# Aquarium-controller.net
KiCad netlist of a schematic drawn in EAGLE
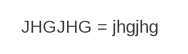
[diagram p0: schematic, sheet 1, part 1 of 2]
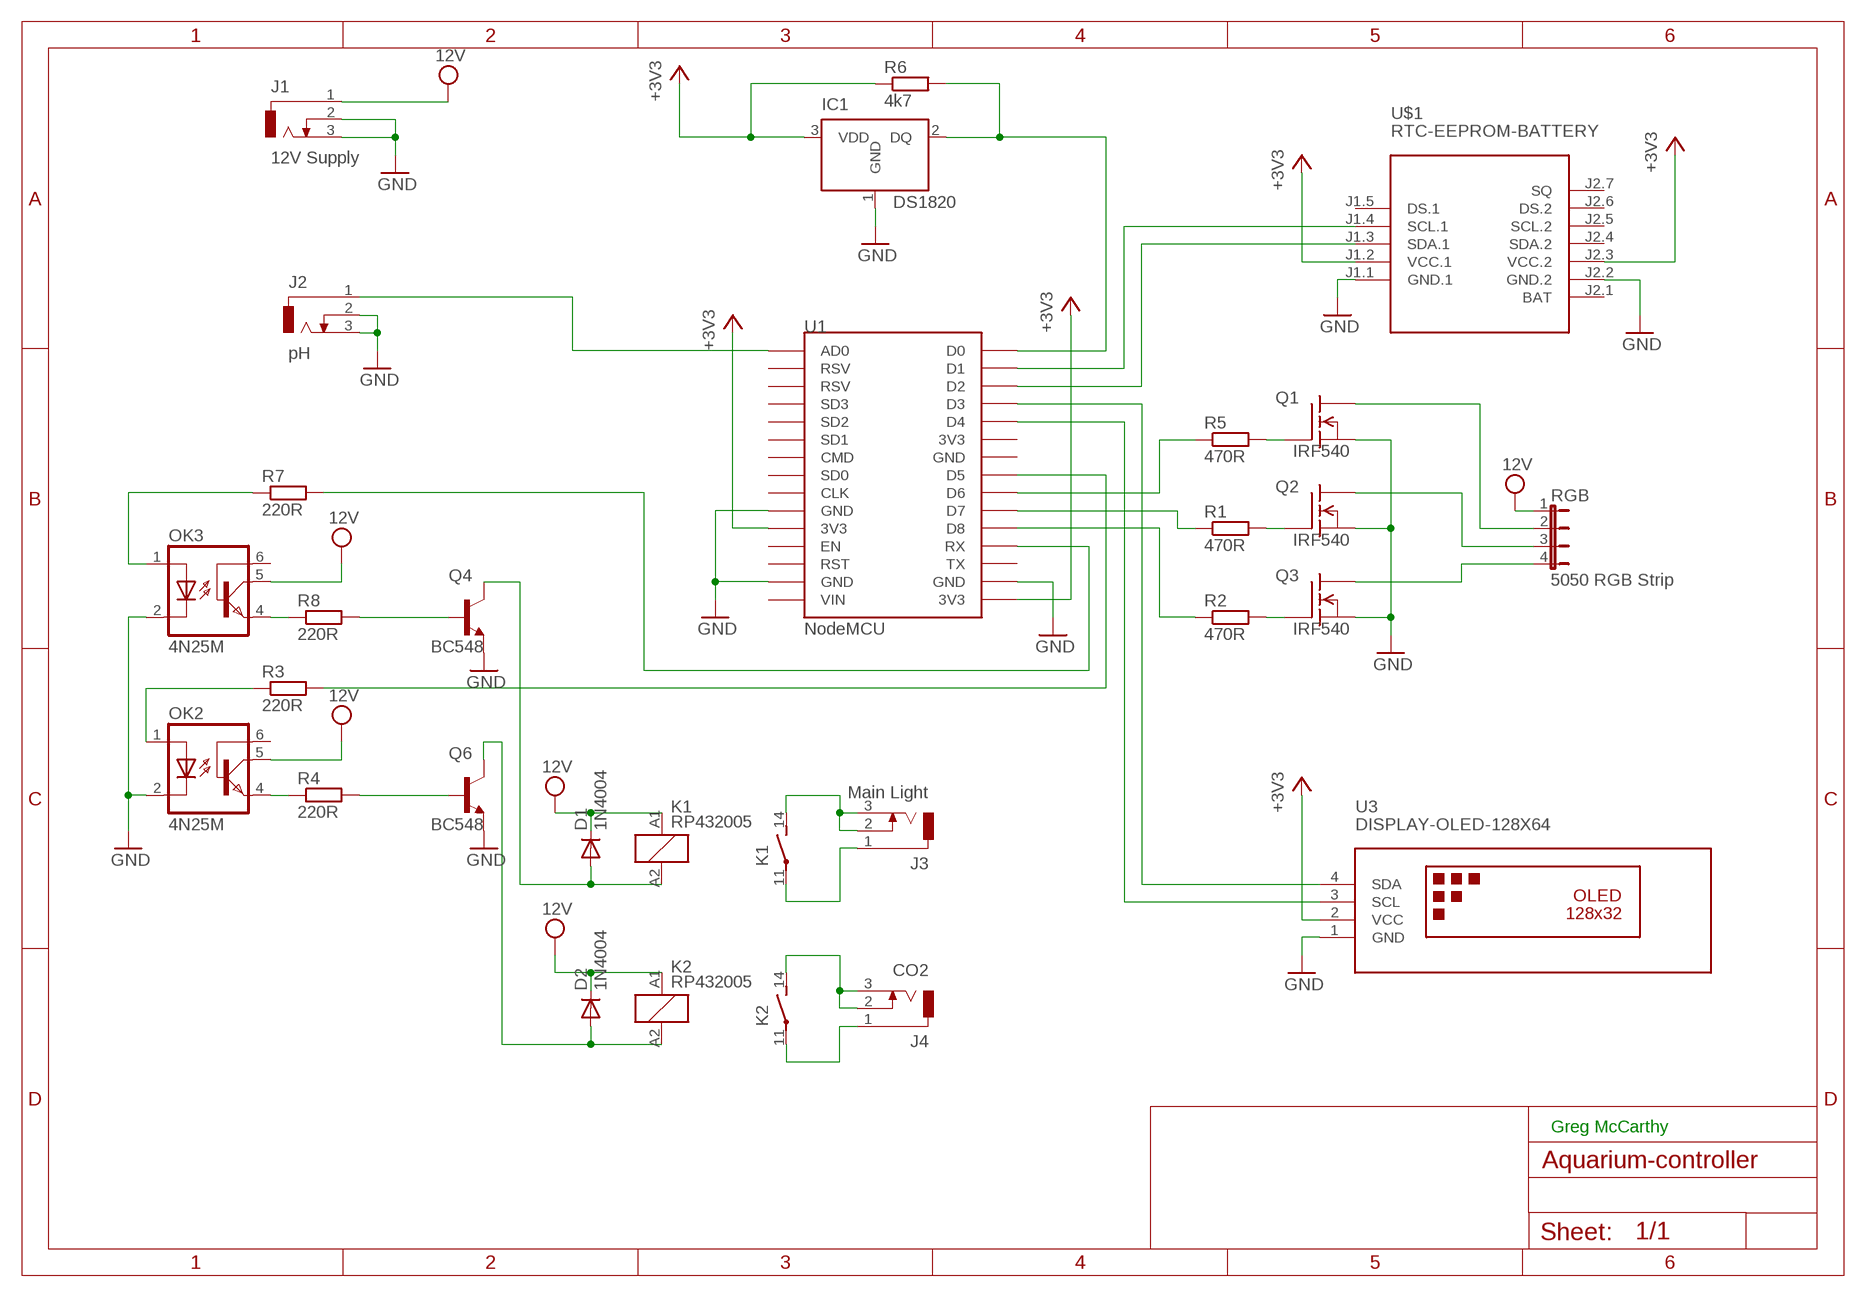
[diagram p1: schematic, sheet 1, part 2 of 2]

(export (version "E")
  (design (tool "Eeschema 10.0.6"))
  (components
    (comp (ref "D1")
      (value "1N4004")
      (footprint "eagle-import:DO41-10")
      (libsource (lib "eagle-import") (part "1N4004"))
    )
    (comp (ref "D2")
      (value "1N4004")
      (footprint "eagle-import:DO41-10")
      (libsource (lib "eagle-import") (part "1N4004"))
    )
    (comp (ref "IC1")
      (value "DS1820")
      (footprint "eagle-import:TO-92")
      (libsource (lib "eagle-import") (part "DS1820"))
    )
    (comp (ref "J1")
      (value "12V Supply")
      (footprint "eagle-import:DCJ0202")
      (libsource (lib "eagle-import") (part "DCJ0202"))
    )
    (comp (ref "J2")
      (value "pH")
      (footprint "eagle-import:DCJ0202")
      (libsource (lib "eagle-import") (part "DCJ0202"))
    )
    (comp (ref "J3")
      (value "Main Light")
      (footprint "eagle-import:DCJ0202")
      (libsource (lib "eagle-import") (part "DCJ0202"))
    )
    (comp (ref "J4")
      (value "CO2")
      (footprint "eagle-import:DCJ0202")
      (libsource (lib "eagle-import") (part "DCJ0202"))
    )
    (comp (ref "K1")
      (value "RP432005")
      (footprint "eagle-import:RT-N_O12A3.5")
      (libsource (lib "eagle-import") (part "RP?324005"))
    )
    (comp (ref "K2")
      (value "RP432005")
      (footprint "eagle-import:RT-N_O12A3.5")
      (libsource (lib "eagle-import") (part "RP?324005"))
    )
    (comp (ref "OK2")
      (value "4N25M")
      (footprint "eagle-import:DIL06")
      (fields (field (name "MPN") "4N25-M"))
      (libsource (lib "eagle-import") (part "4N?M25"))
    )
    (comp (ref "OK3")
      (value "4N25M")
      (footprint "eagle-import:DIL06")
      (fields (field (name "MPN") "4N25-M"))
      (libsource (lib "eagle-import") (part "4N?M25"))
    )
    (comp (ref "Q1")
      (value "IRF540")
      (footprint "eagle-import:TO220")
      (libsource (lib "eagle-import") (part "IRF540"))
    )
    (comp (ref "Q2")
      (value "IRF540")
      (footprint "eagle-import:TO220")
      (libsource (lib "eagle-import") (part "IRF540"))
    )
    (comp (ref "Q3")
      (value "IRF540")
      (footprint "eagle-import:TO220")
      (libsource (lib "eagle-import") (part "IRF540"))
    )
    (comp (ref "Q4")
      (value "BC548")
      (footprint "eagle-import:TO92-EBC")
      (libsource (lib "eagle-import") (part "BC548"))
    )
    (comp (ref "Q6")
      (value "BC548")
      (footprint "eagle-import:TO92-EBC")
      (libsource (lib "eagle-import") (part "BC548"))
    )
    (comp (ref "R1")
      (value "470R")
      (footprint "eagle-import:0204_7")
      (libsource (lib "eagle-import") (part "R0204/7"))
    )
    (comp (ref "R2")
      (value "470R")
      (footprint "eagle-import:0204_7")
      (libsource (lib "eagle-import") (part "R0204/7"))
    )
    (comp (ref "R3")
      (value "220R")
      (footprint "eagle-import:0204_7")
      (libsource (lib "eagle-import") (part "R0204/7"))
    )
    (comp (ref "R4")
      (value "220R")
      (footprint "eagle-import:0204_7")
      (libsource (lib "eagle-import") (part "R0204/7"))
    )
    (comp (ref "R5")
      (value "470R")
      (footprint "eagle-import:0204_7")
      (libsource (lib "eagle-import") (part "R0204/7"))
    )
    (comp (ref "R6")
      (value "4k7")
      (footprint "eagle-import:0204_7")
      (libsource (lib "eagle-import") (part "R0204/7"))
    )
    (comp (ref "R7")
      (value "220R")
      (footprint "eagle-import:0204_7")
      (libsource (lib "eagle-import") (part "R0204/7"))
    )
    (comp (ref "R8")
      (value "220R")
      (footprint "eagle-import:0204_7")
      (libsource (lib "eagle-import") (part "R0204/7"))
    )
    (comp (ref "RGB")
      (value "5050 RGB Strip")
      (footprint "eagle-import:JP4")
      (libsource (lib "eagle-import") (part "JP4E"))
    )
    (comp (ref "U$1")
      (value "RTC-EEPROM-BATTERY")
      (footprint "eagle-import:RTC-EEPROM-BATTERY")
      (libsource (lib "eagle-import") (part "RTC-EEPROM-BATTERY"))
    )
    (comp (ref "U1")
      (value "NodeMCU")
      (footprint "eagle-import:ESP12E_DEVKIT")
      (libsource (lib "eagle-import") (part "ESP12E_DEVKIT"))
    )
    (comp (ref "U3")
      (value "DISPLAY-OLED-128X64")
      (footprint "eagle-import:DISPLAY-OLED-128X32")
      (libsource (lib "eagle-import") (part "DISPLAY-OLED-128X32"))
    )
  )
  (nets
    (net (code "1") (name "+3V3") (class "Default")
      (node (ref "IC1") (pin "3") (pinfunction "VDD_3") (pintype "input"))
      (node (ref "R6") (pin "1") (pinfunction "1_1") (pintype "passive"))
      (node (ref "U$1") (pin "J1.2") (pinfunction "VCC.1_J1.2") (pintype "power_in"))
      (node (ref "U$1") (pin "J2.3") (pinfunction "VCC.2_J2.3") (pintype "power_in"))
      (node (ref "U1") (pin "3V3@0") (pinfunction "3V3_3V3@0") (pintype "bidirectional"))
      (node (ref "U1") (pin "3V3@2") (pinfunction "3V3_3V3@2") (pintype "bidirectional"))
      (node (ref "U3") (pin "2") (pinfunction "VCC_2") (pintype "power_in"))
    )
    (net (code "2") (name "12V") (class "Default")
      (node (ref "D1") (pin "C") (pinfunction "C_C") (pintype "passive"))
      (node (ref "D2") (pin "C") (pinfunction "C_C") (pintype "passive"))
      (node (ref "J1") (pin "1") (pinfunction "1_1") (pintype "passive"))
      (node (ref "K1") (pin "A1") (pinfunction "1_A1") (pintype "passive"))
      (node (ref "K2") (pin "A1") (pinfunction "1_A1") (pintype "passive"))
      (node (ref "OK2") (pin "5") (pinfunction "COL_5") (pintype "passive"))
      (node (ref "OK3") (pin "5") (pinfunction "COL_5") (pintype "passive"))
      (node (ref "RGB") (pin "1") (pinfunction "1_1") (pintype "passive"))
    )
    (net (code "3") (name "GND") (class "Default")
      (node (ref "IC1") (pin "1") (pinfunction "GND_1") (pintype "power_in"))
      (node (ref "J1") (pin "2") (pinfunction "2_2") (pintype "passive"))
      (node (ref "J1") (pin "3") (pinfunction "3_3") (pintype "passive"))
      (node (ref "J2") (pin "2") (pinfunction "2_2") (pintype "passive"))
      (node (ref "J2") (pin "3") (pinfunction "3_3") (pintype "passive"))
      (node (ref "OK2") (pin "2") (pinfunction "C_2") (pintype "passive"))
      (node (ref "OK3") (pin "2") (pinfunction "C_2") (pintype "passive"))
      (node (ref "Q1") (pin "3") (pinfunction "S_3") (pintype "passive"))
      (node (ref "Q2") (pin "3") (pinfunction "S_3") (pintype "passive"))
      (node (ref "Q3") (pin "3") (pinfunction "S_3") (pintype "passive"))
      (node (ref "Q4") (pin "E") (pinfunction "E_E") (pintype "passive"))
      (node (ref "Q6") (pin "E") (pinfunction "E_E") (pintype "passive"))
      (node (ref "U$1") (pin "J1.1") (pinfunction "GND.1_J1.1") (pintype "power_in"))
      (node (ref "U$1") (pin "J2.2") (pinfunction "GND.2_J2.2") (pintype "power_in"))
      (node (ref "U1") (pin "GND@0") (pinfunction "GND_GND@0") (pintype "bidirectional"))
      (node (ref "U1") (pin "GND@1") (pinfunction "GND_GND@1") (pintype "bidirectional"))
      (node (ref "U1") (pin "GND@3") (pinfunction "GND_GND@3") (pintype "bidirectional"))
      (node (ref "U3") (pin "1") (pinfunction "GND_1") (pintype "power_in"))
    )
    (net (code "4") (name "Net-(IC1-DQ)") (class "Default")
      (node (ref "IC1") (pin "2") (pinfunction "DQ_2") (pintype "output"))
      (node (ref "R6") (pin "2") (pinfunction "2_2") (pintype "passive"))
      (node (ref "U1") (pin "D0") (pinfunction "D0_D0") (pintype "bidirectional"))
    )
    (net (code "5") (name "Net-(J2-Pad1)") (class "Default")
      (node (ref "J2") (pin "1") (pinfunction "1_1") (pintype "passive"))
      (node (ref "U1") (pin "AD0") (pinfunction "AD0_AD0") (pintype "bidirectional"))
    )
    (net (code "6") (name "Net-(K1A-2)") (class "Default")
      (node (ref "D1") (pin "A") (pinfunction "A_A") (pintype "passive"))
      (node (ref "K1") (pin "A2") (pinfunction "2_A2") (pintype "passive"))
      (node (ref "Q4") (pin "C") (pinfunction "C_C") (pintype "passive"))
    )
    (net (code "7") (name "Net-(K1B-P)") (class "Default")
      (node (ref "J3") (pin "1") (pinfunction "1_1") (pintype "passive"))
      (node (ref "K1") (pin "11") (pinfunction "P_11") (pintype "passive"))
    )
    (net (code "8") (name "Net-(K1B-S)") (class "Default")
      (node (ref "J3") (pin "2") (pinfunction "2_2") (pintype "passive"))
      (node (ref "J3") (pin "3") (pinfunction "3_3") (pintype "passive"))
      (node (ref "K1") (pin "14") (pinfunction "S_14") (pintype "passive"))
    )
    (net (code "9") (name "Net-(K2A-2)") (class "Default")
      (node (ref "D2") (pin "A") (pinfunction "A_A") (pintype "passive"))
      (node (ref "K2") (pin "A2") (pinfunction "2_A2") (pintype "passive"))
      (node (ref "Q6") (pin "C") (pinfunction "C_C") (pintype "passive"))
    )
    (net (code "10") (name "Net-(K2B-P)") (class "Default")
      (node (ref "J4") (pin "1") (pinfunction "1_1") (pintype "passive"))
      (node (ref "K2") (pin "11") (pinfunction "P_11") (pintype "passive"))
    )
    (net (code "11") (name "Net-(K2B-S)") (class "Default")
      (node (ref "J4") (pin "2") (pinfunction "2_2") (pintype "passive"))
      (node (ref "J4") (pin "3") (pinfunction "3_3") (pintype "passive"))
      (node (ref "K2") (pin "14") (pinfunction "S_14") (pintype "passive"))
    )
    (net (code "12") (name "Net-(OK2-A)") (class "Default")
      (node (ref "OK2") (pin "1") (pinfunction "A_1") (pintype "passive"))
      (node (ref "R3") (pin "1") (pinfunction "1_1") (pintype "passive"))
    )
    (net (code "13") (name "Net-(OK2-EMI)") (class "Default")
      (node (ref "OK2") (pin "4") (pinfunction "EMI_4") (pintype "passive"))
      (node (ref "R4") (pin "1") (pinfunction "1_1") (pintype "passive"))
    )
    (net (code "14") (name "Net-(OK3-A)") (class "Default")
      (node (ref "OK3") (pin "1") (pinfunction "A_1") (pintype "passive"))
      (node (ref "R7") (pin "1") (pinfunction "1_1") (pintype "passive"))
    )
    (net (code "15") (name "Net-(OK3-EMI)") (class "Default")
      (node (ref "OK3") (pin "4") (pinfunction "EMI_4") (pintype "passive"))
      (node (ref "R8") (pin "1") (pinfunction "1_1") (pintype "passive"))
    )
    (net (code "16") (name "Net-(Q1-D)") (class "Default")
      (node (ref "Q1") (pin "2") (pinfunction "D_2") (pintype "passive"))
      (node (ref "RGB") (pin "2") (pinfunction "2_2") (pintype "passive"))
    )
    (net (code "17") (name "Net-(Q1-G)") (class "Default")
      (node (ref "Q1") (pin "1") (pinfunction "G_1") (pintype "passive"))
      (node (ref "R5") (pin "2") (pinfunction "2_2") (pintype "passive"))
    )
    (net (code "18") (name "Net-(Q2-D)") (class "Default")
      (node (ref "Q2") (pin "2") (pinfunction "D_2") (pintype "passive"))
      (node (ref "RGB") (pin "3") (pinfunction "3_3") (pintype "passive"))
    )
    (net (code "19") (name "Net-(Q2-G)") (class "Default")
      (node (ref "Q2") (pin "1") (pinfunction "G_1") (pintype "passive"))
      (node (ref "R1") (pin "2") (pinfunction "2_2") (pintype "passive"))
    )
    (net (code "20") (name "Net-(Q3-D)") (class "Default")
      (node (ref "Q3") (pin "2") (pinfunction "D_2") (pintype "passive"))
      (node (ref "RGB") (pin "4") (pinfunction "4_4") (pintype "passive"))
    )
    (net (code "21") (name "Net-(Q3-G)") (class "Default")
      (node (ref "Q3") (pin "1") (pinfunction "G_1") (pintype "passive"))
      (node (ref "R2") (pin "2") (pinfunction "2_2") (pintype "passive"))
    )
    (net (code "22") (name "Net-(Q4-PadB)") (class "Default")
      (node (ref "Q4") (pin "B") (pinfunction "B_B") (pintype "passive"))
      (node (ref "R8") (pin "2") (pinfunction "2_2") (pintype "passive"))
    )
    (net (code "23") (name "Net-(Q6-PadB)") (class "Default")
      (node (ref "Q6") (pin "B") (pinfunction "B_B") (pintype "passive"))
      (node (ref "R4") (pin "2") (pinfunction "2_2") (pintype "passive"))
    )
    (net (code "24") (name "Net-(R1-Pad1)") (class "Default")
      (node (ref "R1") (pin "1") (pinfunction "1_1") (pintype "passive"))
      (node (ref "U1") (pin "D7") (pinfunction "D7_D7") (pintype "bidirectional"))
    )
    (net (code "25") (name "Net-(R2-Pad1)") (class "Default")
      (node (ref "R2") (pin "1") (pinfunction "1_1") (pintype "passive"))
      (node (ref "U1") (pin "D8") (pinfunction "D8_D8") (pintype "bidirectional"))
    )
    (net (code "26") (name "Net-(R3-Pad2)") (class "Default")
      (node (ref "R3") (pin "2") (pinfunction "2_2") (pintype "passive"))
      (node (ref "U1") (pin "D5") (pinfunction "D5_D5") (pintype "bidirectional"))
    )
    (net (code "27") (name "Net-(R5-Pad1)") (class "Default")
      (node (ref "R5") (pin "1") (pinfunction "1_1") (pintype "passive"))
      (node (ref "U1") (pin "D6") (pinfunction "D6_D6") (pintype "bidirectional"))
    )
    (net (code "28") (name "Net-(R7-Pad2)") (class "Default")
      (node (ref "R7") (pin "2") (pinfunction "2_2") (pintype "passive"))
      (node (ref "U1") (pin "RX") (pinfunction "RX_RX") (pintype "bidirectional"))
    )
    (net (code "29") (name "Net-(U$1-SCL.1)") (class "Default")
      (node (ref "U$1") (pin "J1.4") (pinfunction "SCL.1_J1.4") (pintype "bidirectional"))
      (node (ref "U1") (pin "D1") (pinfunction "D1_D1") (pintype "bidirectional"))
    )
    (net (code "30") (name "Net-(U$1-SDA.1)") (class "Default")
      (node (ref "U$1") (pin "J1.3") (pinfunction "SDA.1_J1.3") (pintype "bidirectional"))
      (node (ref "U1") (pin "D2") (pinfunction "D2_D2") (pintype "bidirectional"))
    )
    (net (code "31") (name "Net-(U3-SCL)") (class "Default")
      (node (ref "U1") (pin "D4") (pinfunction "D4_D4") (pintype "bidirectional"))
      (node (ref "U3") (pin "3") (pinfunction "SCL_3") (pintype "bidirectional"))
    )
    (net (code "32") (name "Net-(U3-SDA)") (class "Default")
      (node (ref "U1") (pin "D3") (pinfunction "D3_D3") (pintype "bidirectional"))
      (node (ref "U3") (pin "4") (pinfunction "SDA_4") (pintype "bidirectional"))
    )
    (net (code "33") (name "unconnected-(OK2-BAS-Pad6)") (class "Default")
      (node (ref "OK2") (pin "6") (pinfunction "BAS_6") (pintype "passive"))
    )
    (net (code "34") (name "unconnected-(OK3-BAS-Pad6)") (class "Default")
      (node (ref "OK3") (pin "6") (pinfunction "BAS_6") (pintype "passive"))
    )
    (net (code "35") (name "unconnected-(U$1-BAT-PadJ2.1)") (class "Default")
      (node (ref "U$1") (pin "J2.1") (pinfunction "BAT_J2.1") (pintype "bidirectional"))
    )
    (net (code "36") (name "unconnected-(U$1-DS.1-PadJ1.5)") (class "Default")
      (node (ref "U$1") (pin "J1.5") (pinfunction "DS.1_J1.5") (pintype "bidirectional"))
    )
    (net (code "37") (name "unconnected-(U$1-DS.2-PadJ2.6)") (class "Default")
      (node (ref "U$1") (pin "J2.6") (pinfunction "DS.2_J2.6") (pintype "bidirectional"))
    )
    (net (code "38") (name "unconnected-(U$1-SCL.2-PadJ2.5)") (class "Default")
      (node (ref "U$1") (pin "J2.5") (pinfunction "SCL.2_J2.5") (pintype "bidirectional"))
    )
    (net (code "39") (name "unconnected-(U$1-SDA.2-PadJ2.4)") (class "Default")
      (node (ref "U$1") (pin "J2.4") (pinfunction "SDA.2_J2.4") (pintype "bidirectional"))
    )
    (net (code "40") (name "unconnected-(U$1-SQ-PadJ2.7)") (class "Default")
      (node (ref "U$1") (pin "J2.7") (pinfunction "SQ_J2.7") (pintype "bidirectional"))
    )
    (net (code "41") (name "unconnected-(U1-3V3-Pad3V3@1)") (class "Default")
      (node (ref "U1") (pin "3V3@1") (pinfunction "3V3_3V3@1") (pintype "bidirectional"))
    )
    (net (code "42") (name "unconnected-(U1-GND-PadGND@2)") (class "Default")
      (node (ref "U1") (pin "GND@2") (pinfunction "GND_GND@2") (pintype "bidirectional"))
    )
    (net (code "43") (name "unconnected-(U1-PadCLK)") (class "Default")
      (node (ref "U1") (pin "CLK") (pinfunction "CLK_CLK") (pintype "bidirectional"))
    )
    (net (code "44") (name "unconnected-(U1-PadCMD)") (class "Default")
      (node (ref "U1") (pin "CMD") (pinfunction "CMD_CMD") (pintype "bidirectional"))
    )
    (net (code "45") (name "unconnected-(U1-PadEN)") (class "Default")
      (node (ref "U1") (pin "EN") (pinfunction "EN_EN") (pintype "bidirectional"))
    )
    (net (code "46") (name "unconnected-(U1-PadRST)") (class "Default")
      (node (ref "U1") (pin "RST") (pinfunction "RST_RST") (pintype "bidirectional"))
    )
    (net (code "47") (name "unconnected-(U1-PadSD0)") (class "Default")
      (node (ref "U1") (pin "SD0") (pinfunction "SD0_SD0") (pintype "bidirectional"))
    )
    (net (code "48") (name "unconnected-(U1-PadSD1)") (class "Default")
      (node (ref "U1") (pin "SD1") (pinfunction "SD1_SD1") (pintype "bidirectional"))
    )
    (net (code "49") (name "unconnected-(U1-PadSD2)") (class "Default")
      (node (ref "U1") (pin "SD2") (pinfunction "SD2_SD2") (pintype "bidirectional"))
    )
    (net (code "50") (name "unconnected-(U1-PadSD3)") (class "Default")
      (node (ref "U1") (pin "SD3") (pinfunction "SD3_SD3") (pintype "bidirectional"))
    )
    (net (code "51") (name "unconnected-(U1-PadTX)") (class "Default")
      (node (ref "U1") (pin "TX") (pinfunction "TX_TX") (pintype "bidirectional"))
    )
    (net (code "52") (name "unconnected-(U1-PadVIN)") (class "Default")
      (node (ref "U1") (pin "VIN") (pinfunction "VIN_VIN") (pintype "bidirectional"))
    )
    (net (code "53") (name "unconnected-(U1-RSV-PadRSV@0)") (class "Default")
      (node (ref "U1") (pin "RSV@0") (pinfunction "RSV_RSV@0") (pintype "bidirectional"))
    )
    (net (code "54") (name "unconnected-(U1-RSV-PadRSV@1)") (class "Default")
      (node (ref "U1") (pin "RSV@1") (pinfunction "RSV_RSV@1") (pintype "bidirectional"))
    )
  )
)
